# PoweSupply.net
KiCad netlist of a schematic drawn in Altium Designer
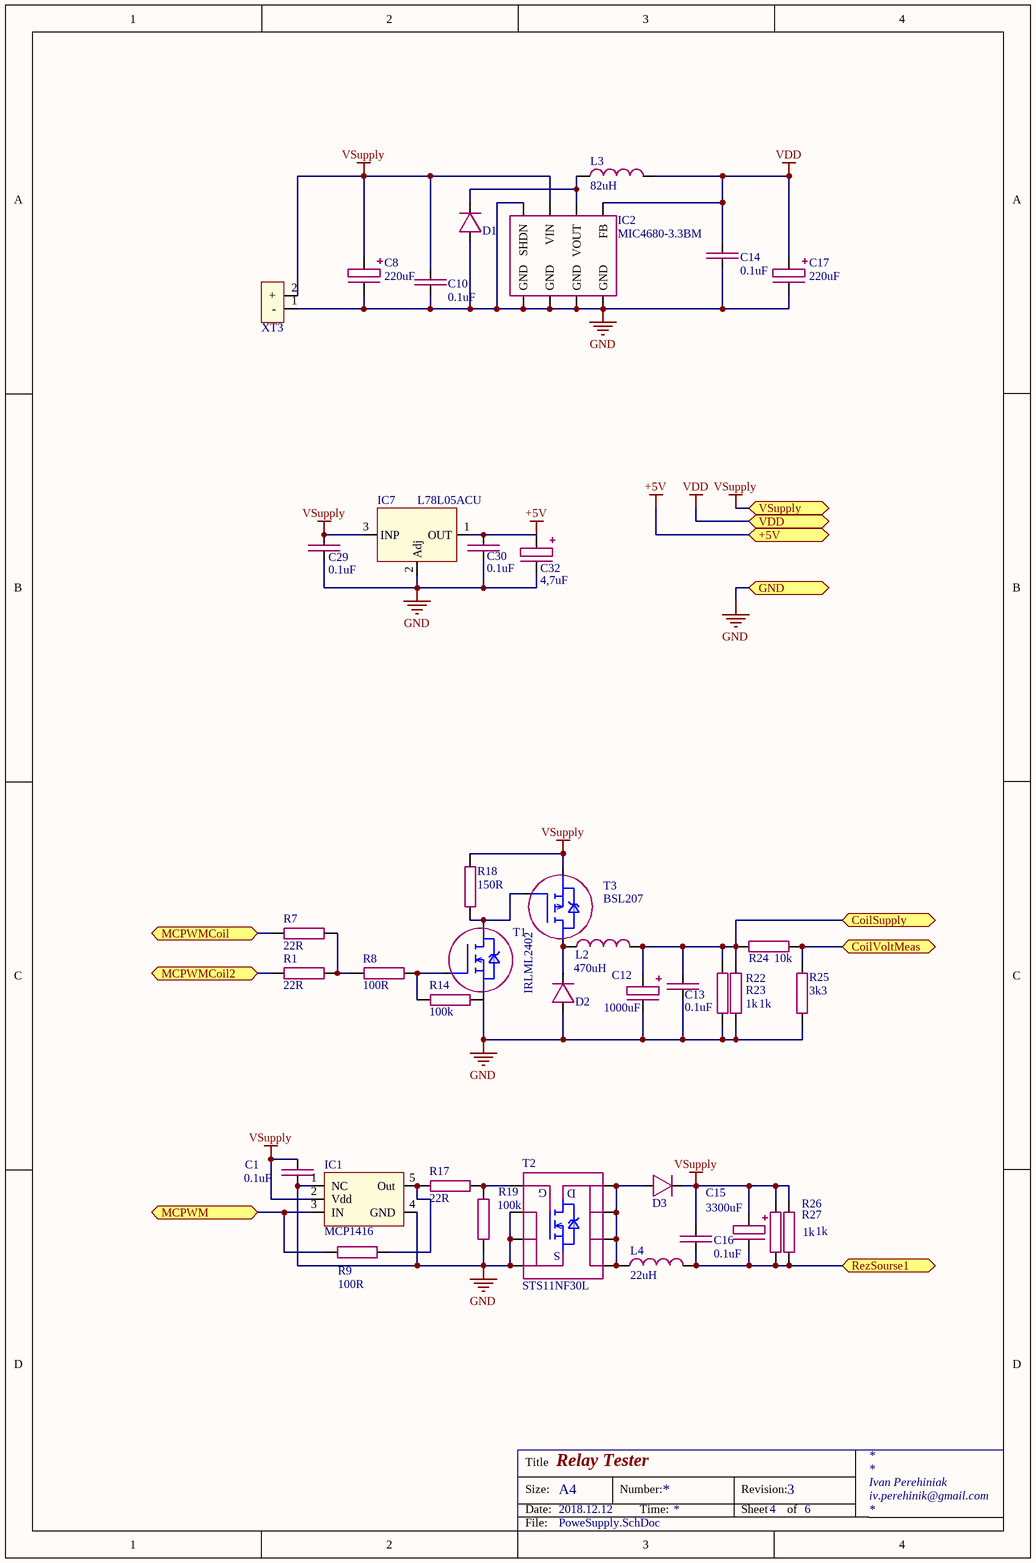
[diagram p0: PoweSupply.SchDoc]

(export (version "E")
  (design (tool "Eeschema 10.0.6"))
  (components
    (comp (ref "C1")
      (value "0.1uF")
      (footprint "PcbLib:C0603")
      (description "CAP CER 0.1UF 50V X7R 0603")
      (fields (field (name "MANUFACTURER PART NUMBER") "GMK316F475ZG-T"))
      (libsource (lib "RCU") (part "GMK316F475ZG-T"))
    )
    (comp (ref "C8")
      (value "220uF")
      (footprint "PcbLib:CAP10x12")
      (description "CAP ALUM 220UF 20% 35V RADIAL")
      (fields (field (name "MANUFACTURER PART NUMBER") "EEU-FC1V221L"))
      (libsource (lib "RCU") (part "EEU-FC1V221L"))
    )
    (comp (ref "C10")
      (value "0.1uF")
      (footprint "PcbLib:C0603")
      (description "CAP CER 0.1UF 50V X7R 0603")
      (fields (field (name "MANUFACTURER PART NUMBER") "GMK316F475ZG-T"))
      (libsource (lib "RCU") (part "GMK316F475ZG-T"))
    )
    (comp (ref "C12")
      (value "1000uF")
      (footprint "PcbLib:CAP10x12")
      (description "CAP ALUM 1000UF 20% 16V RADIAL")
      (fields (field (name "MANUFACTURER PART NUMBER") "CE-1000/16PHT-Y"))
      (libsource (lib "RCU") (part "CE-1000/16PHT-Y"))
    )
    (comp (ref "C13")
      (value "0.1uF")
      (footprint "PcbLib:C0603")
      (description "CAP CER 0.1UF 50V X7R 0603")
      (fields (field (name "MANUFACTURER PART NUMBER") "GMK316F475ZG-T"))
      (libsource (lib "RCU") (part "GMK316F475ZG-T"))
    )
    (comp (ref "C14")
      (value "0.1uF")
      (footprint "PcbLib:C0603")
      (description "CAP CER 0.1UF 50V X7R 0603")
      (fields (field (name "MANUFACTURER PART NUMBER") "GMK316F475ZG-T"))
      (libsource (lib "RCU") (part "GMK316F475ZG-T"))
    )
    (comp (ref "C15")
      (value "3300uF")
      (footprint "PcbLib:CAP12.5x20p")
      (description "CAP ALUM 3300UF 20% 16V RADIAL")
      (fields (field (name "MANUFACTURER PART NUMBER") "UVR1C332MHD"))
      (libsource (lib "RCU") (part "UVR1C332MHD"))
    )
    (comp (ref "C16")
      (value "0.1uF")
      (footprint "PcbLib:C0603")
      (description "CAP CER 0.1UF 50V X7R 0603")
      (fields (field (name "MANUFACTURER PART NUMBER") "GMK316F475ZG-T"))
      (libsource (lib "RCU") (part "GMK316F475ZG-T"))
    )
    (comp (ref "C17")
      (value "220uF")
      (footprint "PcbLib:CAP6x11_Hor")
      (description "CAP ALUM 220UF 20% 10V RADIAL")
      (fields (field (name "MANUFACTURER PART NUMBER") "EEUFC1A221SH"))
      (libsource (lib "RCU") (part "EEUFC1A221SH"))
    )
    (comp (ref "C29")
      (value "0.1uF")
      (footprint "PcbLib:C0603")
      (description "CAP CER 0.1UF 50V X7R 0603")
      (fields (field (name "MANUFACTURER PART NUMBER") "GMK316F475ZG-T"))
      (libsource (lib "RCU") (part "GMK316F475ZG-T"))
    )
    (comp (ref "C30")
      (value "0.1uF")
      (footprint "PcbLib:C0603")
      (description "CAP CER 0.1UF 50V X7R 0603")
      (fields (field (name "MANUFACTURER PART NUMBER") "GMK316F475ZG-T"))
      (libsource (lib "RCU") (part "GMK316F475ZG-T"))
    )
    (comp (ref "C32")
      (value "4,7uF")
      (footprint "PcbLib:1206(Tantal A)")
      (description "CAP TANT 4.7UF 10V 10% 1206")
      (fields (field (name "MANUFACTURER PART NUMBER") "T491A475K010AT"))
      (libsource (lib "RCU") (part "T491A475K010AT"))
    )
    (comp (ref "D1")
      (value "B260A-13-F")
      (footprint "PcbLib:SMA")
      (description "DIODE SCHOTTKY 2A 40V SMA")
      (libsource (lib "RCU") (part "B260A-13-F"))
    )
    (comp (ref "D2")
      (value "SK54A-LTP")
      (footprint "PcbLib:SMA")
      (description "DIODE SCHOTTKY 5A 40V SMA")
      (libsource (lib "RCU") (part "SK54A-LTP"))
    )
    (comp (ref "D3")
      (value "SK54A-LTP")
      (footprint "PcbLib:SMA")
      (description "DIODE SCHOTTKY 5A 40V SMA")
      (libsource (lib "RCU") (part "SK54A-LTP"))
    )
    (comp (ref "IC1")
      (value "MCP1416")
      (footprint "PcbLib:SOT23-5")
      (description "IC MOSFET DVR 1.5A HS SOT23-5")
      (fields (field (name "MANUFACTURER PART NUMBER") "MCP1416T-E/OT"))
      (libsource (lib "RCU") (part "MCP1416T-E/OT"))
    )
    (comp (ref "IC2")
      (value "MIC4680-3.3BM")
      (footprint "PcbLib:SOIC_N")
      (description "BUCK CONV 3.3V 1A")
      (libsource (lib "RCU") (part "MIC4680-3.3BM"))
    )
    (comp (ref "IC7")
      (value "L78L05ACU")
      (footprint "PcbLib:SOT89-3")
      (description "IC REG LINEAR 5V 100MA SOT89-3")
      (libsource (lib "RCU") (part "L78L05ACU"))
    )
    (comp (ref "L2")
      (value "470uH")
      (footprint "PcbLib:B82477G4")
      (description "FIXED IND 470UH 1A 741 MOHM SMD")
      (fields (field (name "MANUFACTURER PART NUMBER") "DE1207-390"))
      (libsource (lib "RCU") (part "DE1207-470"))
    )
    (comp (ref "L3")
      (value "82uH")
      (footprint "PcbLib:B82477G4")
      (description "FIXED IND 82UH 1.2A SMD")
      (fields (field (name "MANUFACTURER PART NUMBER") "DE1205-82"))
      (libsource (lib "RCU") (part "DE1205-82"))
    )
    (comp (ref "L4")
      (value "22uH")
      (footprint "PcbLib:B82477G4")
      (description "FIXED IND 22UH 5A 39 MOHM SMD")
      (fields (field (name "MANUFACTURER PART NUMBER") "DE1209-22"))
      (libsource (lib "RCU") (part "DE1209-22"))
    )
    (comp (ref "R1")
      (value "22R")
      (footprint "PcbLib:R0603")
      (description "RES SMD 22 OHM 1% 1/10W 0603")
      (fields (field (name "MANUFACTURER PART NUMBER") "CRCW060322R0FKEA"))
      (libsource (lib "RCU") (part "CRCW060322R0FKEA"))
    )
    (comp (ref "R7")
      (value "22R")
      (footprint "PcbLib:R0603")
      (description "RES SMD 22 OHM 1% 1/10W 0603")
      (fields (field (name "MANUFACTURER PART NUMBER") "CRCW060322R0FKEA"))
      (libsource (lib "RCU") (part "CRCW060322R0FKEA"))
    )
    (comp (ref "R8")
      (value "100R")
      (footprint "PcbLib:R0603")
      (description "RES SMD 100 OHM 5% 1/10W 0603")
      (fields (field (name "MANUFACTURER PART NUMBER") "ERJ-S03J101V"))
      (libsource (lib "RCU") (part "ERJ-S03J101V"))
    )
    (comp (ref "R9")
      (value "100R")
      (footprint "PcbLib:R0603")
      (description "RES SMD 100 OHM 5% 1/10W 0603")
      (fields (field (name "MANUFACTURER PART NUMBER") "ERJ-S03J101V"))
      (libsource (lib "RCU") (part "ERJ-S03J101V"))
    )
    (comp (ref "R14")
      (value "100k")
      (footprint "PcbLib:R0603")
      (description "RES SMD 100K OHM 5% 1/10W 0603")
      (fields (field (name "MANUFACTURER PART NUMBER") "ERJ-S03J104V"))
      (libsource (lib "RCU") (part "ERJ-S03J104V"))
    )
    (comp (ref "R17")
      (value "22R")
      (footprint "PcbLib:R0603")
      (description "RES SMD 22 OHM 1% 1/10W 0603")
      (fields (field (name "MANUFACTURER PART NUMBER") "CRCW060322R0FKEA"))
      (libsource (lib "RCU") (part "CRCW060322R0FKEA"))
    )
    (comp (ref "R18")
      (value "150R")
      (footprint "PcbLib:Resistor_2W-2")
      (description "RES THT 150 OHM 5% 2W")
      (fields (field (name "MANUFACTURER PART NUMBER") "2WT-150OHM"))
      (libsource (lib "RCU") (part "2WT-150OHM"))
    )
    (comp (ref "R19")
      (value "100k")
      (footprint "PcbLib:R0603")
      (description "RES SMD 100K OHM 5% 1/10W 0603")
      (fields (field (name "MANUFACTURER PART NUMBER") "ERJ-S03J104V"))
      (libsource (lib "RCU") (part "ERJ-S03J104V"))
    )
    (comp (ref "R22")
      (value "1k")
      (footprint "R1206")
      (description "RES SMD 1K OHM 5% 1/4W 1206")
      (fields (field (name "MANUFACTURER PART NUMBER") "ERJ-8GEYJ102V"))
      (libsource (lib "RCU") (part "ERJ-8GEYJ102V"))
    )
    (comp (ref "R23")
      (value "1k")
      (footprint "R1206")
      (description "RES SMD 1K OHM 5% 1/4W 1206")
      (fields (field (name "MANUFACTURER PART NUMBER") "ERJ-8GEYJ102V"))
      (libsource (lib "RCU") (part "ERJ-8GEYJ102V"))
    )
    (comp (ref "R24")
      (value "10k")
      (footprint "PcbLib:R0603")
      (description "RES SMD 10K OHM 1% 1/10W 0603")
      (fields (field (name "MANUFACTURER PART NUMBER") "CRCW060310K0FKTABC"))
      (libsource (lib "RCU") (part "CRCW060310K0FKTABC"))
    )
    (comp (ref "R25")
      (value "3k3")
      (footprint "PcbLib:R0603")
      (description "RES SMD 3.3K OHM 1% 1/10W 0603")
      (fields (field (name "MANUFACTURER PART NUMBER") "CRCW06033K30FKTABC"))
      (libsource (lib "RCU") (part "CRCW06033K30FKTABC"))
    )
    (comp (ref "R26")
      (value "1k")
      (footprint "R1206")
      (description "RES SMD 1K OHM 5% 1/4W 1206")
      (fields (field (name "MANUFACTURER PART NUMBER") "ERJ-8GEYJ102V"))
      (libsource (lib "RCU") (part "ERJ-8GEYJ102V"))
    )
    (comp (ref "R27")
      (value "1k")
      (footprint "R1206")
      (description "RES SMD 1K OHM 5% 1/4W 1206")
      (fields (field (name "MANUFACTURER PART NUMBER") "ERJ-8GEYJ102V"))
      (libsource (lib "RCU") (part "ERJ-8GEYJ102V"))
    )
    (comp (ref "T1")
      (value "IRLML2402")
      (footprint "PcbLib:SOT-23")
      (description "MOSFET N-CH 20V 1.2A SOT-23")
      (fields (field (name "MANUFACTURER PART NUMBER") "IRLML2402TRPBF"))
      (libsource (lib "RCU") (part "IRLML2402TRPBF"))
    )
    (comp (ref "T2")
      (value "STS11NF30L")
      (footprint "PcbLib:SOIC_N")
      (description "MOSFET N-CH 30V 11A 8-SOIC")
      (libsource (lib "RCU") (part "STS11NF30L"))
    )
    (comp (ref "T3")
      (value "BSL207")
      (footprint "PcbLib:SOT23-6 - mosfet")
      (description "MOSFET P-CH 20V 6A 6TSOP")
      (fields (field (name "MANUFACTURER PART NUMBER") "BSL207SPH6327XTSA1"))
      (libsource (lib "RCU") (part "BSL207SPH6327XTSA1"))
    )
    (comp (ref "XT3")
      (value "PowerJack5,5/2,1mm")
      (footprint "PcbLib:PowerJack5.5x2.1")
      (description "SIL VERTICAL PC TAIL PIN HEADER")
      (fields (field (name "MANUFACTURER PART NUMBER") "FC68148"))
      (libsource (lib "RCU") (part "PowerJack5,5/2,1mm"))
    )
  )
  (nets
    (net (code "1") (name "+5V") (class "Default")
      (node (ref "C30") (pin "2") (pinfunction "2_2") (pintype "passive"))
      (node (ref "C32") (pin "1") (pinfunction "+_1") (pintype "passive"))
      (node (ref "IC7") (pin "1") (pinfunction "OUT_1") (pintype "passive"))
    )
    (net (code "2") (name "/CoilSupply") (class "Default")
      (node (ref "C12") (pin "1") (pinfunction "+_1") (pintype "passive"))
      (node (ref "C13") (pin "2") (pinfunction "2_2") (pintype "passive"))
      (node (ref "L2") (pin "2") (pinfunction "2_2") (pintype "passive"))
      (node (ref "R22") (pin "2") (pinfunction "2_2") (pintype "passive"))
      (node (ref "R23") (pin "2") (pinfunction "2_2") (pintype "passive"))
      (node (ref "R24") (pin "1") (pinfunction "1_1") (pintype "passive"))
    )
    (net (code "3") (name "/CoilVoltMeas") (class "Default")
      (node (ref "R24") (pin "2") (pinfunction "2_2") (pintype "passive"))
      (node (ref "R25") (pin "2") (pinfunction "2_2") (pintype "passive"))
    )
    (net (code "4") (name "/MCPWM") (class "Default")
      (node (ref "IC1") (pin "3") (pinfunction "IN_3") (pintype "passive"))
      (node (ref "R9") (pin "1") (pinfunction "1_1") (pintype "passive"))
    )
    (net (code "5") (name "/MCPWMCoil") (class "Default")
      (node (ref "R7") (pin "1") (pinfunction "1_1") (pintype "passive"))
    )
    (net (code "6") (name "/MCPWMCoil2") (class "Default")
      (node (ref "R1") (pin "2") (pinfunction "2_2") (pintype "passive"))
    )
    (net (code "7") (name "/RezSourse1") (class "Default")
      (node (ref "C15") (pin "2") (pinfunction "-_2") (pintype "passive"))
      (node (ref "C16") (pin "2") (pinfunction "2_2") (pintype "passive"))
      (node (ref "L4") (pin "2") (pinfunction "2_2") (pintype "passive"))
      (node (ref "R26") (pin "1") (pinfunction "1_1") (pintype "passive"))
      (node (ref "R27") (pin "1") (pinfunction "1_1") (pintype "passive"))
    )
    (net (code "8") (name "GND") (class "Default")
      (node (ref "C1") (pin "2") (pinfunction "2_2") (pintype "passive"))
      (node (ref "C10") (pin "1") (pinfunction "1_1") (pintype "passive"))
      (node (ref "C12") (pin "2") (pinfunction "-_2") (pintype "passive"))
      (node (ref "C13") (pin "1") (pinfunction "1_1") (pintype "passive"))
      (node (ref "C14") (pin "1") (pinfunction "1_1") (pintype "passive"))
      (node (ref "C17") (pin "2") (pinfunction "-_2") (pintype "passive"))
      (node (ref "C29") (pin "1") (pinfunction "1_1") (pintype "passive"))
      (node (ref "C30") (pin "1") (pinfunction "1_1") (pintype "passive"))
      (node (ref "C32") (pin "2") (pinfunction "-_2") (pintype "passive"))
      (node (ref "C8") (pin "2") (pinfunction "-_2") (pintype "passive"))
      (node (ref "D1") (pin "1") (pinfunction "Anode_1") (pintype "passive"))
      (node (ref "D2") (pin "1") (pinfunction "Anode_1") (pintype "passive"))
      (node (ref "IC1") (pin "1") (pinfunction "NC_1") (pintype "passive"))
      (node (ref "IC1") (pin "4") (pinfunction "GND_4") (pintype "passive"))
      (node (ref "IC2") (pin "1") (pinfunction "SHDN_1") (pintype "passive"))
      (node (ref "IC2") (pin "5") (pinfunction "GND_5") (pintype "passive"))
      (node (ref "IC2") (pin "6") (pinfunction "GND_6") (pintype "passive"))
      (node (ref "IC2") (pin "7") (pinfunction "GND_7") (pintype "passive"))
      (node (ref "IC2") (pin "8") (pinfunction "GND_8") (pintype "passive"))
      (node (ref "IC7") (pin "2") (pinfunction "Adj_2") (pintype "passive"))
      (node (ref "R14") (pin "2") (pinfunction "2_2") (pintype "passive"))
      (node (ref "R19") (pin "1") (pinfunction "1_1") (pintype "passive"))
      (node (ref "R22") (pin "1") (pinfunction "1_1") (pintype "passive"))
      (node (ref "R23") (pin "1") (pinfunction "1_1") (pintype "passive"))
      (node (ref "R25") (pin "1") (pinfunction "1_1") (pintype "passive"))
      (node (ref "T1") (pin "2") (pinfunction "SOURSE_2") (pintype "passive"))
      (node (ref "T2") (pin "1") (pinfunction "SOURSE_1") (pintype "passive"))
      (node (ref "T2") (pin "2") (pinfunction "SOURSE_2") (pintype "passive"))
      (node (ref "T2") (pin "3") (pinfunction "SOURSE_3") (pintype "passive"))
      (node (ref "XT3") (pin "1") (pinfunction "-_1") (pintype "passive"))
    )
    (net (code "9") (name "Net-(D1-Cathode)") (class "Default")
      (node (ref "D1") (pin "2") (pinfunction "Cathode_2") (pintype "passive"))
      (node (ref "IC2") (pin "3") (pinfunction "VOUT_3") (pintype "passive"))
      (node (ref "L3") (pin "1") (pinfunction "1_1") (pintype "passive"))
    )
    (net (code "10") (name "Net-(D2-Cathode)") (class "Default")
      (node (ref "D2") (pin "2") (pinfunction "Cathode_2") (pintype "passive"))
      (node (ref "L2") (pin "1") (pinfunction "1_1") (pintype "passive"))
      (node (ref "T3") (pin "2") (pinfunction "DRAIN_2") (pintype "passive"))
    )
    (net (code "11") (name "Net-(D3-Anode)") (class "Default")
      (node (ref "D3") (pin "1") (pinfunction "Anode_1") (pintype "passive"))
      (node (ref "L4") (pin "1") (pinfunction "1_1") (pintype "passive"))
      (node (ref "T2") (pin "5") (pinfunction "DRAIN_5") (pintype "passive"))
      (node (ref "T2") (pin "6") (pinfunction "DRAIN_6") (pintype "passive"))
      (node (ref "T2") (pin "7") (pinfunction "DRAIN_7") (pintype "passive"))
      (node (ref "T2") (pin "8") (pinfunction "DRAIN_8") (pintype "passive"))
    )
    (net (code "12") (name "Net-(IC1-Out)") (class "Default")
      (node (ref "IC1") (pin "5") (pinfunction "Out_5") (pintype "passive"))
      (node (ref "R17") (pin "1") (pinfunction "1_1") (pintype "passive"))
      (node (ref "R9") (pin "2") (pinfunction "2_2") (pintype "passive"))
    )
    (net (code "13") (name "Net-(R1-Pad1)") (class "Default")
      (node (ref "R1") (pin "1") (pinfunction "1_1") (pintype "passive"))
      (node (ref "R7") (pin "2") (pinfunction "2_2") (pintype "passive"))
      (node (ref "R8") (pin "1") (pinfunction "1_1") (pintype "passive"))
    )
    (net (code "14") (name "Net-(T1-DRAIN)") (class "Default")
      (node (ref "R18") (pin "1") (pinfunction "1_1") (pintype "passive"))
      (node (ref "T1") (pin "3") (pinfunction "DRAIN_3") (pintype "passive"))
      (node (ref "T3") (pin "1") (pinfunction "GATE_1") (pintype "passive"))
    )
    (net (code "15") (name "Net-(T1-GATE)") (class "Default")
      (node (ref "R14") (pin "1") (pinfunction "1_1") (pintype "passive"))
      (node (ref "R8") (pin "2") (pinfunction "2_2") (pintype "passive"))
      (node (ref "T1") (pin "1") (pinfunction "GATE_1") (pintype "passive"))
    )
    (net (code "16") (name "Net-(T2-GATE)") (class "Default")
      (node (ref "R17") (pin "2") (pinfunction "2_2") (pintype "passive"))
      (node (ref "R19") (pin "2") (pinfunction "2_2") (pintype "passive"))
      (node (ref "T2") (pin "4") (pinfunction "GATE_4") (pintype "passive"))
    )
    (net (code "17") (name "VDD") (class "Default")
      (node (ref "C14") (pin "2") (pinfunction "2_2") (pintype "passive"))
      (node (ref "C17") (pin "1") (pinfunction "+_1") (pintype "passive"))
      (node (ref "IC2") (pin "4") (pinfunction "FB_4") (pintype "passive"))
      (node (ref "L3") (pin "2") (pinfunction "2_2") (pintype "passive"))
    )
    (net (code "18") (name "VSupply") (class "Default")
      (node (ref "C1") (pin "1") (pinfunction "1_1") (pintype "passive"))
      (node (ref "C10") (pin "2") (pinfunction "2_2") (pintype "passive"))
      (node (ref "C15") (pin "1") (pinfunction "+_1") (pintype "passive"))
      (node (ref "C16") (pin "1") (pinfunction "1_1") (pintype "passive"))
      (node (ref "C29") (pin "2") (pinfunction "2_2") (pintype "passive"))
      (node (ref "C8") (pin "1") (pinfunction "+_1") (pintype "passive"))
      (node (ref "D3") (pin "2") (pinfunction "Cathode_2") (pintype "passive"))
      (node (ref "IC1") (pin "2") (pinfunction "Vdd_2") (pintype "passive"))
      (node (ref "IC2") (pin "2") (pinfunction "VIN_2") (pintype "passive"))
      (node (ref "IC7") (pin "3") (pinfunction "INP_3") (pintype "passive"))
      (node (ref "R18") (pin "2") (pinfunction "2_2") (pintype "passive"))
      (node (ref "R26") (pin "2") (pinfunction "2_2") (pintype "passive"))
      (node (ref "R27") (pin "2") (pinfunction "2_2") (pintype "passive"))
      (node (ref "T3") (pin "3") (pinfunction "SOURSE_3") (pintype "passive"))
      (node (ref "XT3") (pin "2") (pinfunction "+_2") (pintype "passive"))
    )
  )
)
